# ATX_Power_Breakout.net
KiCad netlist of a schematic drawn in EAGLE
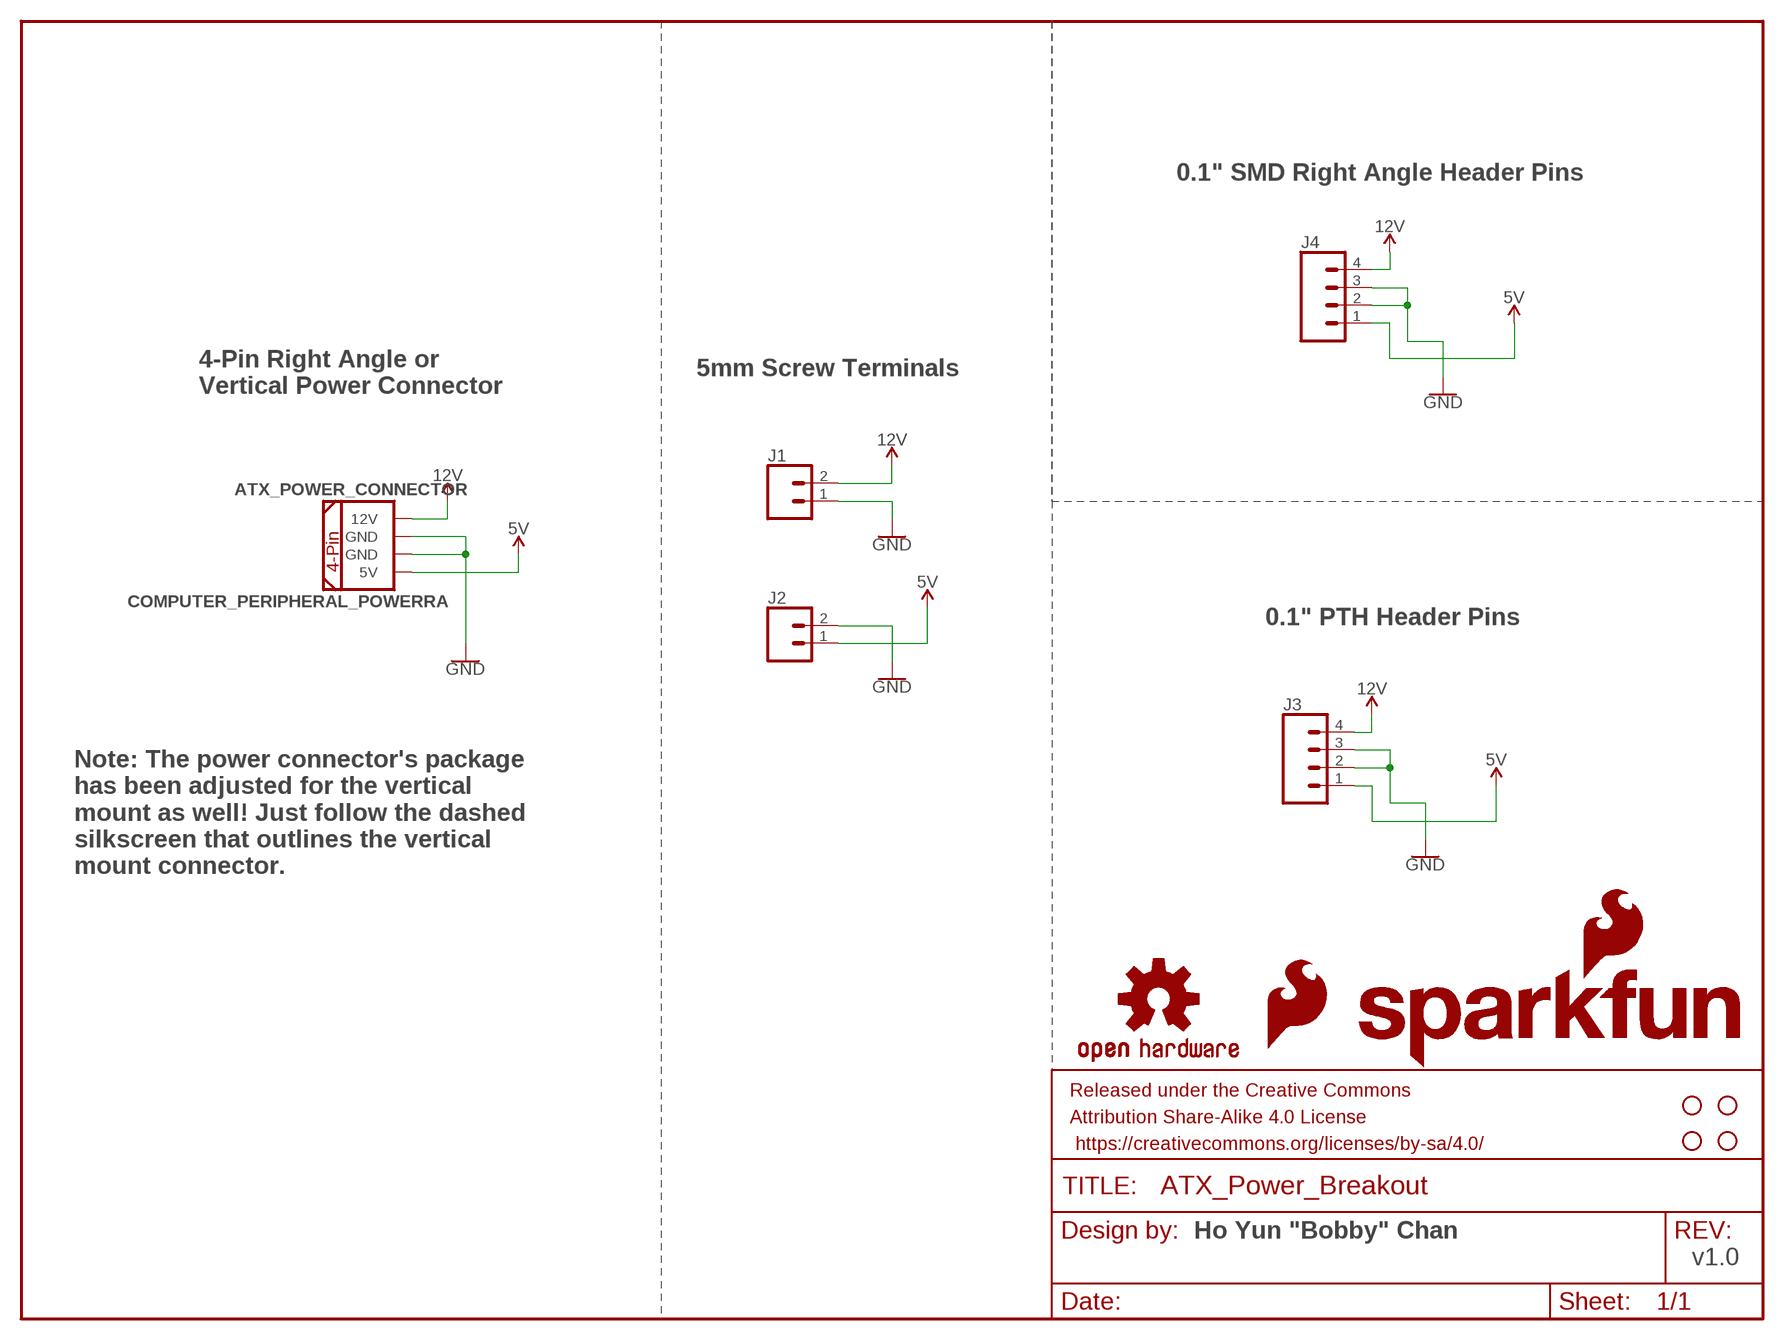
[diagram p0: schematic, sheet 1]

(export (version "E")
  (design (tool "Eeschema 10.0.6"))
  (components
    (comp (ref "ATX_POWER_CONNECTOR")
      (value "COMPUTER_PERIPHERAL_POWERRA")
      (footprint "eagle-import:COMPUTER-PERIPHERAL-POWER-RA")
      (libsource (lib "eagle-import") (part "COMPUTER_PERIPHERAL_POWERRA"))
    )
    (comp (ref "FRAME1")
      (value "FRAME-LETTER")
      (footprint "eagle-import:CREATIVE_COMMONS")
      (libsource (lib "eagle-import") (part "FRAME-LETTER"))
    )
    (comp (ref "H1")
      (value "STAND-OFF")
      (footprint "eagle-import:STAND-OFF")
      (libsource (lib "eagle-import") (part "STAND-OFF"))
    )
    (comp (ref "H2")
      (value "STAND-OFF")
      (footprint "eagle-import:STAND-OFF")
      (libsource (lib "eagle-import") (part "STAND-OFF"))
    )
    (comp (ref "H3")
      (value "STAND-OFF")
      (footprint "eagle-import:STAND-OFF")
      (libsource (lib "eagle-import") (part "STAND-OFF"))
    )
    (comp (ref "H4")
      (value "STAND-OFF")
      (footprint "eagle-import:STAND-OFF")
      (libsource (lib "eagle-import") (part "STAND-OFF"))
    )
    (comp (ref "J1")
      (value "CONN_025MM")
      (footprint "eagle-import:SCREWTERMINAL-5MM-2")
      (libsource (lib "eagle-import") (part "CONN_025MM"))
    )
    (comp (ref "J2")
      (value "CONN_025MM")
      (footprint "eagle-import:SCREWTERMINAL-5MM-2")
      (libsource (lib "eagle-import") (part "CONN_025MM"))
    )
    (comp (ref "J3")
      (value "CONN_04")
      (footprint "eagle-import:1X04")
      (libsource (lib "eagle-import") (part "CONN_04"))
    )
    (comp (ref "J4")
      (value "CONN_04SMD")
      (footprint "eagle-import:1X04_SMD_RA_MALE")
      (libsource (lib "eagle-import") (part "CONN_04SMD"))
    )
    (comp (ref "LOGO1")
      (value "OSHW-LOGOS")
      (footprint "eagle-import:OSHW-LOGO-S")
      (libsource (lib "eagle-import") (part "OSHW-LOGOS"))
    )
    (comp (ref "LOGO2")
      (value "SFE_LOGO_NAME_FLAME.1_INCH")
      (footprint "eagle-import:SFE_LOGO_NAME_FLAME_.1")
      (libsource (lib "eagle-import") (part "SFE_LOGO_NAME_FLAME.1_INCH"))
    )
    (comp (ref "LOGO3")
      (value "SFE_LOGO_FLAME.1_INCH")
      (footprint "eagle-import:SFE_LOGO_FLAME_.1")
      (libsource (lib "eagle-import") (part "SFE_LOGO_FLAME.1_INCH"))
    )
  )
  (nets
    (net (code "1") (name "5V") (class "Default")
      (node (ref "ATX_POWER_CONNECTOR") (pin "5V") (pinfunction "5V_5V") (pintype "passive"))
      (node (ref "J2") (pin "1") (pinfunction "1_1") (pintype "passive"))
      (node (ref "J3") (pin "1") (pinfunction "1_1") (pintype "passive"))
      (node (ref "J4") (pin "1") (pinfunction "1_1") (pintype "passive"))
    )
    (net (code "2") (name "12V") (class "Default")
      (node (ref "ATX_POWER_CONNECTOR") (pin "12V") (pinfunction "12V_12V") (pintype "passive"))
      (node (ref "J1") (pin "2") (pinfunction "2_2") (pintype "passive"))
      (node (ref "J3") (pin "4") (pinfunction "4_4") (pintype "passive"))
      (node (ref "J4") (pin "4") (pinfunction "4_4") (pintype "passive"))
    )
    (net (code "3") (name "GND") (class "Default")
      (node (ref "ATX_POWER_CONNECTOR") (pin "GND@1") (pinfunction "GND_GND@1") (pintype "passive"))
      (node (ref "ATX_POWER_CONNECTOR") (pin "GND@2") (pinfunction "GND_GND@2") (pintype "passive"))
      (node (ref "J1") (pin "1") (pinfunction "1_1") (pintype "passive"))
      (node (ref "J2") (pin "2") (pinfunction "2_2") (pintype "passive"))
      (node (ref "J3") (pin "2") (pinfunction "2_2") (pintype "passive"))
      (node (ref "J3") (pin "3") (pinfunction "3_3") (pintype "passive"))
      (node (ref "J4") (pin "2") (pinfunction "2_2") (pintype "passive"))
      (node (ref "J4") (pin "3") (pinfunction "3_3") (pintype "passive"))
    )
  )
)
